# Sheet1.net
KiCad netlist of a schematic drawn in Altium Designer
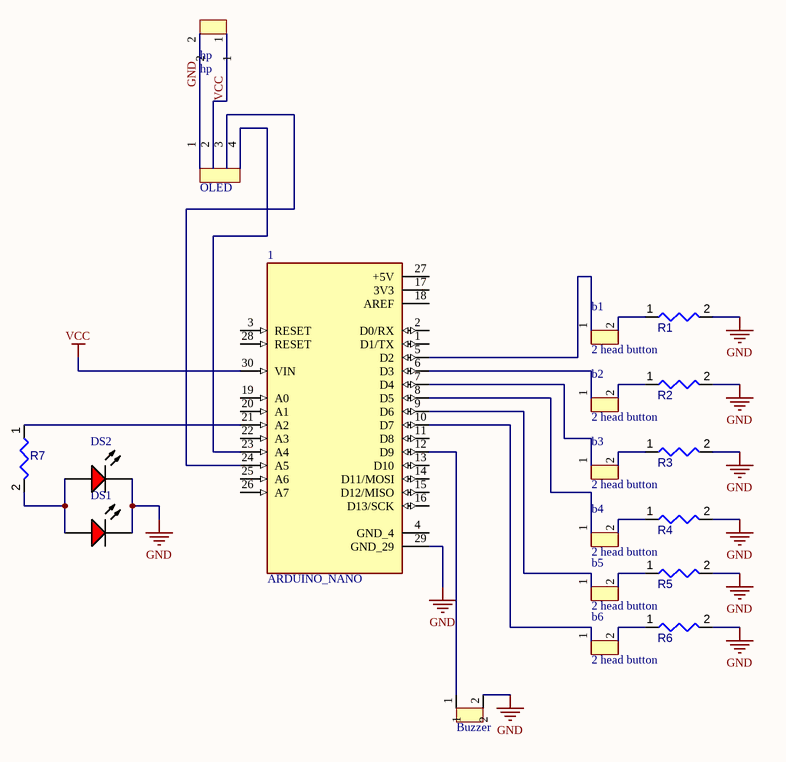
[diagram p0: Sheet1.SchDoc]

(export (version "E")
  (design (tool "Eeschema 10.0.6"))
  (components
    (comp (ref "1")
      (value "ARDUINO_NANO")
      (footprint "MODULE_ARDUINO_NANO")
      (description "Small, complete, and breadboard-friendly board based on the ATmega328 (Arduino Nano 3.x)")
      (fields (field (name "MP") "Arduino Nano") (field (name "MF") "Arduino"))
      (libsource (lib "Chase Rubin") (part "ARDUINO_NANO"))
    )
    (comp (ref "b1")
      (value "2 head button")
      (footprint "2 head button")
      (libsource (lib "Schlib1") (part "2 head button"))
    )
    (comp (ref "b2")
      (value "2 head button")
      (footprint "2 head button")
      (libsource (lib "Schlib1") (part "2 head button"))
    )
    (comp (ref "b3")
      (value "2 head button")
      (footprint "2 head button")
      (libsource (lib "Schlib1") (part "2 head button"))
    )
    (comp (ref "b4")
      (value "2 head button")
      (footprint "2 head button")
      (libsource (lib "Schlib1") (part "2 head button"))
    )
    (comp (ref "b5")
      (value "2 head button")
      (footprint "2 head button")
      (libsource (lib "Schlib1") (part "2 head button"))
    )
    (comp (ref "b6")
      (value "2 head button")
      (footprint "2 head button")
      (libsource (lib "Schlib1") (part "2 head button"))
    )
    (comp (ref "Buzzer") (value "Buzzer") (footprint "buzzer") (libsource (lib "Schlib1") (part "Buzzer")))
    (comp (ref "DS1")
      (value "LTL-1CHE")
      (footprint "INDPR60-254-520X380X650")
      (description "LED Uni-Color Red, 100 mW, 30 mA, -55 to 100 degC, 2-Pin THD, RoHS, Bulk")
      (fields (field (name "MANUFACTURER") "Lite-On"))
      (libsource (lib "Chase Rubin") (part "LED-RED-AK-2"))
    )
    (comp (ref "DS2")
      (value "LTL-1CHE")
      (footprint "INDPR60-254-520X380X650")
      (description "LED Uni-Color Red, 100 mW, 30 mA, -55 to 100 degC, 2-Pin THD, RoHS, Bulk")
      (fields (field (name "MANUFACTURER") "Lite-On"))
      (libsource (lib "Chase Rubin") (part "LED-RED-AK-2"))
    )
    (comp (ref "hp") (value "hp") (footprint "hp") (libsource (lib "Schlib1") (part "hp")))
    (comp (ref "OLED") (value "OLED") (footprint "OLED") (libsource (lib "Schlib1") (part "OLED")))
    (comp (ref "R1")
      (value "Resistors")
      (footprint "RESA86-1060X240")
      (description "Resistor")
      (libsource (lib "Chase Rubin") (part "RES-2"))
    )
    (comp (ref "R2")
      (value "Resistors")
      (footprint "RESA86-1060X240")
      (description "Resistor")
      (libsource (lib "Chase Rubin") (part "RES-2"))
    )
    (comp (ref "R3")
      (value "Resistors")
      (footprint "RESA86-1060X240")
      (description "Resistor")
      (libsource (lib "Chase Rubin") (part "RES-2"))
    )
    (comp (ref "R4")
      (value "Resistors")
      (footprint "RESA86-1060X240")
      (description "Resistor")
      (libsource (lib "Chase Rubin") (part "RES-2"))
    )
    (comp (ref "R5")
      (value "Resistors")
      (footprint "RESA86-1060X240")
      (description "Resistor")
      (libsource (lib "Chase Rubin") (part "RES-2"))
    )
    (comp (ref "R6")
      (value "Resistors")
      (footprint "RESA86-1060X240")
      (description "Resistor")
      (libsource (lib "Chase Rubin") (part "RES-2"))
    )
    (comp (ref "R7")
      (value "Resistors")
      (footprint "RESA86-1060X240")
      (description "Resistor")
      (libsource (lib "Chase Rubin") (part "RES-2"))
    )
  )
  (nets
    (net (code "1") (name "GND") (class "Default")
      (node (ref "1") (pin "29") (pinfunction "GND_29_29") (pintype "power_in"))
      (node (ref "Buzzer") (pin "2") (pinfunction "2_2") (pintype "passive"))
      (node (ref "DS1") (pin "2") (pinfunction "K_2") (pintype "passive"))
      (node (ref "DS2") (pin "2") (pinfunction "K_2") (pintype "passive"))
      (node (ref "OLED") (pin "1") (pinfunction "1_1") (pintype "passive"))
      (node (ref "R1") (pin "2") (pinfunction "2_2") (pintype "passive"))
      (node (ref "R2") (pin "2") (pinfunction "2_2") (pintype "passive"))
      (node (ref "R3") (pin "2") (pinfunction "2_2") (pintype "passive"))
      (node (ref "R4") (pin "2") (pinfunction "2_2") (pintype "passive"))
      (node (ref "R5") (pin "2") (pinfunction "2_2") (pintype "passive"))
      (node (ref "R6") (pin "2") (pinfunction "2_2") (pintype "passive"))
      (node (ref "hp") (pin "2") (pinfunction "2_2") (pintype "passive"))
    )
    (net (code "2") (name "Net-(1-A2)") (class "Default")
      (node (ref "1") (pin "21") (pinfunction "A2_21") (pintype "input"))
      (node (ref "R7") (pin "1") (pinfunction "1_1") (pintype "passive"))
    )
    (net (code "3") (name "Net-(1-A4)") (class "Default")
      (node (ref "1") (pin "23") (pinfunction "A4_23") (pintype "input"))
      (node (ref "OLED") (pin "4") (pinfunction "4_4") (pintype "passive"))
    )
    (net (code "4") (name "Net-(1-A5)") (class "Default")
      (node (ref "1") (pin "24") (pinfunction "A5_24") (pintype "input"))
      (node (ref "OLED") (pin "3") (pinfunction "3_3") (pintype "passive"))
    )
    (net (code "5") (name "Net-(1-D2)") (class "Default")
      (node (ref "1") (pin "5") (pinfunction "D2_5") (pintype "bidirectional"))
      (node (ref "b1") (pin "1") (pinfunction "1_1") (pintype "passive"))
    )
    (net (code "6") (name "Net-(1-D3)") (class "Default")
      (node (ref "1") (pin "6") (pinfunction "D3_6") (pintype "bidirectional"))
      (node (ref "b2") (pin "1") (pinfunction "1_1") (pintype "passive"))
    )
    (net (code "7") (name "Net-(1-D4)") (class "Default")
      (node (ref "1") (pin "7") (pinfunction "D4_7") (pintype "bidirectional"))
      (node (ref "b3") (pin "1") (pinfunction "1_1") (pintype "passive"))
    )
    (net (code "8") (name "Net-(1-D5)") (class "Default")
      (node (ref "1") (pin "8") (pinfunction "D5_8") (pintype "bidirectional"))
      (node (ref "b4") (pin "1") (pinfunction "1_1") (pintype "passive"))
    )
    (net (code "9") (name "Net-(1-D6)") (class "Default")
      (node (ref "1") (pin "9") (pinfunction "D6_9") (pintype "bidirectional"))
      (node (ref "b5") (pin "1") (pinfunction "1_1") (pintype "passive"))
    )
    (net (code "10") (name "Net-(1-D7)") (class "Default")
      (node (ref "1") (pin "10") (pinfunction "D7_10") (pintype "bidirectional"))
      (node (ref "b6") (pin "1") (pinfunction "1_1") (pintype "passive"))
    )
    (net (code "11") (name "Net-(1-D9)") (class "Default")
      (node (ref "1") (pin "12") (pinfunction "D9_12") (pintype "bidirectional"))
      (node (ref "Buzzer") (pin "1") (pinfunction "1_1") (pintype "passive"))
    )
    (net (code "12") (name "Net-(DS1-A)") (class "Default")
      (node (ref "DS1") (pin "1") (pinfunction "A_1") (pintype "passive"))
      (node (ref "DS2") (pin "1") (pinfunction "A_1") (pintype "passive"))
      (node (ref "R7") (pin "2") (pinfunction "2_2") (pintype "passive"))
    )
    (net (code "13") (name "Net-(R1-Pad1)") (class "Default")
      (node (ref "R1") (pin "1") (pinfunction "1_1") (pintype "passive"))
      (node (ref "b1") (pin "2") (pinfunction "2_2") (pintype "passive"))
    )
    (net (code "14") (name "Net-(R2-Pad1)") (class "Default")
      (node (ref "R2") (pin "1") (pinfunction "1_1") (pintype "passive"))
      (node (ref "b2") (pin "2") (pinfunction "2_2") (pintype "passive"))
    )
    (net (code "15") (name "Net-(R3-Pad1)") (class "Default")
      (node (ref "R3") (pin "1") (pinfunction "1_1") (pintype "passive"))
      (node (ref "b3") (pin "2") (pinfunction "2_2") (pintype "passive"))
    )
    (net (code "16") (name "Net-(R4-Pad1)") (class "Default")
      (node (ref "R4") (pin "1") (pinfunction "1_1") (pintype "passive"))
      (node (ref "b4") (pin "2") (pinfunction "2_2") (pintype "passive"))
    )
    (net (code "17") (name "Net-(R5-Pad1)") (class "Default")
      (node (ref "R5") (pin "1") (pinfunction "1_1") (pintype "passive"))
      (node (ref "b5") (pin "2") (pinfunction "2_2") (pintype "passive"))
    )
    (net (code "18") (name "Net-(R6-Pad1)") (class "Default")
      (node (ref "R6") (pin "1") (pinfunction "1_1") (pintype "passive"))
      (node (ref "b6") (pin "2") (pinfunction "2_2") (pintype "passive"))
    )
    (net (code "19") (name "VCC") (class "Default")
      (node (ref "1") (pin "30") (pinfunction "VIN_30") (pintype "input"))
      (node (ref "OLED") (pin "2") (pinfunction "2_2") (pintype "passive"))
      (node (ref "hp") (pin "1") (pinfunction "1_1") (pintype "passive"))
    )
    (net (code "20") (name "unconnected-(1-+5V-Pad27)") (class "Default")
      (node (ref "1") (pin "27") (pinfunction "+5V_27") (pintype "power_in"))
    )
    (net (code "21") (name "unconnected-(1-3V3-Pad17)") (class "Default")
      (node (ref "1") (pin "17") (pinfunction "3V3_17") (pintype "power_in"))
    )
    (net (code "22") (name "unconnected-(1-A0-Pad19)") (class "Default")
      (node (ref "1") (pin "19") (pinfunction "A0_19") (pintype "input"))
    )
    (net (code "23") (name "unconnected-(1-A1-Pad20)") (class "Default")
      (node (ref "1") (pin "20") (pinfunction "A1_20") (pintype "input"))
    )
    (net (code "24") (name "unconnected-(1-A3-Pad22)") (class "Default")
      (node (ref "1") (pin "22") (pinfunction "A3_22") (pintype "input"))
    )
    (net (code "25") (name "unconnected-(1-A6-Pad25)") (class "Default")
      (node (ref "1") (pin "25") (pinfunction "A6_25") (pintype "input"))
    )
    (net (code "26") (name "unconnected-(1-A7-Pad26)") (class "Default")
      (node (ref "1") (pin "26") (pinfunction "A7_26") (pintype "input"))
    )
    (net (code "27") (name "unconnected-(1-AREF-Pad18)") (class "Default")
      (node (ref "1") (pin "18") (pinfunction "AREF_18") (pintype "power_in"))
    )
    (net (code "28") (name "unconnected-(1-D0{slash}RX-Pad2)") (class "Default")
      (node (ref "1") (pin "2") (pinfunction "D0/RX_2") (pintype "bidirectional"))
    )
    (net (code "29") (name "unconnected-(1-D1{slash}TX-Pad1)") (class "Default")
      (node (ref "1") (pin "1") (pinfunction "D1/TX_1") (pintype "bidirectional"))
    )
    (net (code "30") (name "unconnected-(1-D8-Pad11)") (class "Default")
      (node (ref "1") (pin "11") (pinfunction "D8_11") (pintype "bidirectional"))
    )
    (net (code "31") (name "unconnected-(1-D10-Pad13)") (class "Default")
      (node (ref "1") (pin "13") (pinfunction "D10_13") (pintype "bidirectional"))
    )
    (net (code "32") (name "unconnected-(1-D11{slash}MOSI-Pad14)") (class "Default")
      (node (ref "1") (pin "14") (pinfunction "D11/MOSI_14") (pintype "bidirectional"))
    )
    (net (code "33") (name "unconnected-(1-D12{slash}MISO-Pad15)") (class "Default")
      (node (ref "1") (pin "15") (pinfunction "D12/MISO_15") (pintype "bidirectional"))
    )
    (net (code "34") (name "unconnected-(1-D13{slash}SCK-Pad16)") (class "Default")
      (node (ref "1") (pin "16") (pinfunction "D13/SCK_16") (pintype "bidirectional"))
    )
    (net (code "35") (name "unconnected-(1-GND_4-Pad4)") (class "Default")
      (node (ref "1") (pin "4") (pinfunction "GND_4_4") (pintype "power_in"))
    )
    (net (code "36") (name "unconnected-(1-RESET-Pad3)") (class "Default")
      (node (ref "1") (pin "3") (pinfunction "RESET_3") (pintype "input"))
    )
    (net (code "37") (name "unconnected-(1-RESET-Pad28)") (class "Default")
      (node (ref "1") (pin "28") (pinfunction "RESET_28") (pintype "input"))
    )
  )
)
